# reciever.net
KiCad netlist of a schematic drawn in Altium Designer
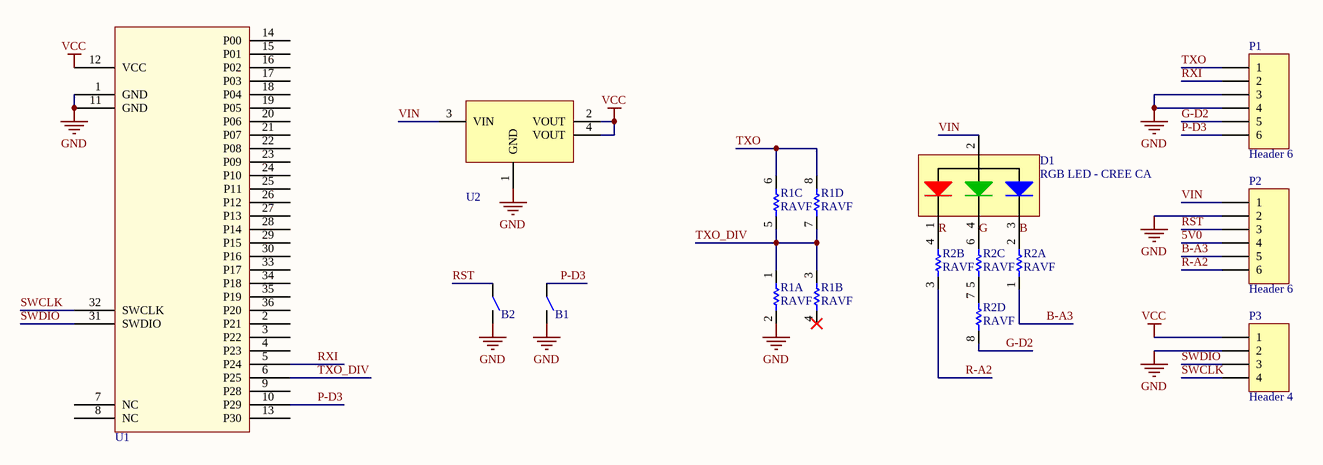
[diagram p0: reciever.SchDoc]

(export (version "E")
  (design (tool "Eeschema 10.0.6"))
  (components
    (comp (ref "B1")
      (value "Tactile Button")
      (footprint "TACTILE BUTTON")
      (libsource (lib "SK") (part "Tactile Button"))
    )
    (comp (ref "B2")
      (value "Tactile Button")
      (footprint "TACTILE BUTTON")
      (libsource (lib "SK") (part "Tactile Button"))
    )
    (comp (ref "D1")
      (value "RGB LED - CREE CA")
      (footprint "PLCC4-RGBLED")
      (description "Tri Colour CA RGB LEDs - CLV1A-FKB")
      (libsource (lib "SK") (part "RGB LED - CREE CA"))
    )
    (comp (ref "P1")
      (value "Header 6")
      (footprint "HDR1X6")
      (description "Header, 6-Pin")
      (fields (field (name "PUBLISHER") "Altium Limited"))
      (libsource (lib "Miscellaneous Connectors") (part "Header 6"))
    )
    (comp (ref "P2")
      (value "Header 6")
      (footprint "HDR1X6")
      (description "Header, 6-Pin")
      (fields (field (name "PUBLISHER") "Altium Limited"))
      (libsource (lib "Miscellaneous Connectors") (part "Header 6"))
    )
    (comp (ref "P3")
      (value "Header 4")
      (footprint "HDR1X4")
      (description "Header, 4-Pin")
      (fields (field (name "PUBLISHER") "Altium Limited"))
      (libsource (lib "Miscellaneous Connectors") (part "Header 4"))
    )
    (comp (ref "R1")
      (value "RAVF")
      (footprint "1206 quad res")
      (description "RAVF164DJT100R")
      (libsource (lib "SK") (part "RAVF_Multi"))
    )
    (comp (ref "R2")
      (value "RAVF")
      (footprint "1206 quad res")
      (description "RAVF164DJT100R")
      (libsource (lib "SK") (part "RAVF_Multi"))
    )
    (comp (ref "U1")
      (value "Core51822 (B)")
      (footprint "Core51822 (B)")
      (description "NRF51822 (B)")
      (libsource (lib "SK") (part "Core51822 (B)"))
    )
    (comp (ref "U2")
      (value "NCP1117")
      (footprint "SOT230P700X180-4N")
      (libsource (lib "SK") (part "NCP1117"))
    )
  )
  (nets
    (net (code "1") (name "/5V0") (class "Default")
      (node (ref "P2") (pin "4") (pinfunction "4_4") (pintype "passive"))
    )
    (net (code "2") (name "/B") (class "Default")
      (node (ref "D1") (pin "3") (pinfunction "B_3") (pintype "passive"))
      (node (ref "R2") (pin "2") (pinfunction "2_2") (pintype "passive"))
    )
    (net (code "3") (name "/B-A3") (class "Default")
      (node (ref "P2") (pin "5") (pinfunction "5_5") (pintype "passive"))
      (node (ref "R2") (pin "1") (pinfunction "1_1") (pintype "passive"))
    )
    (net (code "4") (name "/G") (class "Default")
      (node (ref "D1") (pin "4") (pinfunction "G_4") (pintype "passive"))
      (node (ref "R2") (pin "6") (pinfunction "2_6") (pintype "passive"))
    )
    (net (code "5") (name "/G-D2") (class "Default")
      (node (ref "P1") (pin "5") (pinfunction "5_5") (pintype "passive"))
      (node (ref "R2") (pin "8") (pinfunction "2_8") (pintype "passive"))
    )
    (net (code "6") (name "/P-D3") (class "Default")
      (node (ref "B1") (pin "1") (pinfunction "1_1") (pintype "passive"))
      (node (ref "P1") (pin "6") (pinfunction "6_6") (pintype "passive"))
      (node (ref "U1") (pin "10") (pinfunction "P29_10") (pintype "passive"))
    )
    (net (code "7") (name "/R") (class "Default")
      (node (ref "D1") (pin "1") (pinfunction "R_1") (pintype "passive"))
      (node (ref "R2") (pin "4") (pinfunction "2_4") (pintype "passive"))
    )
    (net (code "8") (name "/R-A2") (class "Default")
      (node (ref "P2") (pin "6") (pinfunction "6_6") (pintype "passive"))
      (node (ref "R2") (pin "3") (pinfunction "1_3") (pintype "passive"))
    )
    (net (code "9") (name "/RST") (class "Default")
      (node (ref "B2") (pin "1") (pinfunction "1_1") (pintype "passive"))
      (node (ref "P2") (pin "3") (pinfunction "3_3") (pintype "passive"))
    )
    (net (code "10") (name "/RXI") (class "Default")
      (node (ref "P1") (pin "2") (pinfunction "2_2") (pintype "passive"))
      (node (ref "U1") (pin "5") (pinfunction "P24_5") (pintype "passive"))
    )
    (net (code "11") (name "/SWCLK") (class "Default")
      (node (ref "P3") (pin "4") (pinfunction "4_4") (pintype "passive"))
      (node (ref "U1") (pin "32") (pinfunction "SWCLK_32") (pintype "passive"))
    )
    (net (code "12") (name "/SWDIO") (class "Default")
      (node (ref "P3") (pin "3") (pinfunction "3_3") (pintype "passive"))
      (node (ref "U1") (pin "31") (pinfunction "SWDIO_31") (pintype "passive"))
    )
    (net (code "13") (name "/TXO") (class "Default")
      (node (ref "P1") (pin "1") (pinfunction "1_1") (pintype "passive"))
      (node (ref "R1") (pin "6") (pinfunction "2_6") (pintype "passive"))
      (node (ref "R1") (pin "8") (pinfunction "2_8") (pintype "passive"))
    )
    (net (code "14") (name "/TXO_DIV") (class "Default")
      (node (ref "R1") (pin "1") (pinfunction "1_1") (pintype "passive"))
      (node (ref "R1") (pin "3") (pinfunction "1_3") (pintype "passive"))
      (node (ref "R1") (pin "5") (pinfunction "1_5") (pintype "passive"))
      (node (ref "R1") (pin "7") (pinfunction "1_7") (pintype "passive"))
      (node (ref "U1") (pin "6") (pinfunction "P25_6") (pintype "passive"))
    )
    (net (code "15") (name "/VIN") (class "Default")
      (node (ref "D1") (pin "2") (pinfunction "CA_2") (pintype "passive"))
      (node (ref "P2") (pin "1") (pinfunction "1_1") (pintype "passive"))
      (node (ref "U2") (pin "3") (pinfunction "VIN_3") (pintype "passive"))
    )
    (net (code "16") (name "GND") (class "Default")
      (node (ref "B1") (pin "2") (pinfunction "2_2") (pintype "passive"))
      (node (ref "B2") (pin "2") (pinfunction "2_2") (pintype "passive"))
      (node (ref "P1") (pin "3") (pinfunction "3_3") (pintype "passive"))
      (node (ref "P1") (pin "4") (pinfunction "4_4") (pintype "passive"))
      (node (ref "P2") (pin "2") (pinfunction "2_2") (pintype "passive"))
      (node (ref "P3") (pin "2") (pinfunction "2_2") (pintype "passive"))
      (node (ref "R1") (pin "2") (pinfunction "2_2") (pintype "passive"))
      (node (ref "U1") (pin "1") (pinfunction "GND_1") (pintype "passive"))
      (node (ref "U1") (pin "11") (pinfunction "GND_11") (pintype "passive"))
      (node (ref "U2") (pin "1") (pinfunction "GND_1") (pintype "passive"))
    )
    (net (code "17") (name "Net-(R2C-1)") (class "Default")
      (node (ref "R2") (pin "5") (pinfunction "1_5") (pintype "passive"))
      (node (ref "R2") (pin "7") (pinfunction "1_7") (pintype "passive"))
    )
    (net (code "18") (name "VCC") (class "Default")
      (node (ref "P3") (pin "1") (pinfunction "1_1") (pintype "passive"))
      (node (ref "U1") (pin "12") (pinfunction "VCC_12") (pintype "passive"))
      (node (ref "U2") (pin "2") (pinfunction "VOUT_2") (pintype "passive"))
      (node (ref "U2") (pin "4") (pinfunction "VOUT_4") (pintype "passive"))
    )
    (net (code "19") (name "unconnected-(R1B-2-Pad4)") (class "Default")
      (node (ref "R1") (pin "4") (pinfunction "2_4") (pintype "passive+no_connect"))
    )
    (net (code "20") (name "unconnected-(U1-NC-Pad7)") (class "Default")
      (node (ref "U1") (pin "7") (pinfunction "NC_7") (pintype "passive"))
    )
    (net (code "21") (name "unconnected-(U1-NC-Pad8)") (class "Default")
      (node (ref "U1") (pin "8") (pinfunction "NC_8") (pintype "passive"))
    )
    (net (code "22") (name "unconnected-(U1-P00-Pad14)") (class "Default")
      (node (ref "U1") (pin "14") (pinfunction "P00_14") (pintype "passive"))
    )
    (net (code "23") (name "unconnected-(U1-P01-Pad15)") (class "Default")
      (node (ref "U1") (pin "15") (pinfunction "P01_15") (pintype "passive"))
    )
    (net (code "24") (name "unconnected-(U1-P02-Pad16)") (class "Default")
      (node (ref "U1") (pin "16") (pinfunction "P02_16") (pintype "passive"))
    )
    (net (code "25") (name "unconnected-(U1-P03-Pad17)") (class "Default")
      (node (ref "U1") (pin "17") (pinfunction "P03_17") (pintype "passive"))
    )
    (net (code "26") (name "unconnected-(U1-P04-Pad18)") (class "Default")
      (node (ref "U1") (pin "18") (pinfunction "P04_18") (pintype "passive"))
    )
    (net (code "27") (name "unconnected-(U1-P05-Pad19)") (class "Default")
      (node (ref "U1") (pin "19") (pinfunction "P05_19") (pintype "passive"))
    )
    (net (code "28") (name "unconnected-(U1-P06-Pad20)") (class "Default")
      (node (ref "U1") (pin "20") (pinfunction "P06_20") (pintype "passive"))
    )
    (net (code "29") (name "unconnected-(U1-P07-Pad21)") (class "Default")
      (node (ref "U1") (pin "21") (pinfunction "P07_21") (pintype "passive"))
    )
    (net (code "30") (name "unconnected-(U1-P08-Pad22)") (class "Default")
      (node (ref "U1") (pin "22") (pinfunction "P08_22") (pintype "passive"))
    )
    (net (code "31") (name "unconnected-(U1-P09-Pad23)") (class "Default")
      (node (ref "U1") (pin "23") (pinfunction "P09_23") (pintype "passive"))
    )
    (net (code "32") (name "unconnected-(U1-P10-Pad24)") (class "Default")
      (node (ref "U1") (pin "24") (pinfunction "P10_24") (pintype "passive"))
    )
    (net (code "33") (name "unconnected-(U1-P11-Pad25)") (class "Default")
      (node (ref "U1") (pin "25") (pinfunction "P11_25") (pintype "passive"))
    )
    (net (code "34") (name "unconnected-(U1-P12-Pad26)") (class "Default")
      (node (ref "U1") (pin "26") (pinfunction "P12_26") (pintype "passive"))
    )
    (net (code "35") (name "unconnected-(U1-P13-Pad27)") (class "Default")
      (node (ref "U1") (pin "27") (pinfunction "P13_27") (pintype "passive"))
    )
    (net (code "36") (name "unconnected-(U1-P14-Pad28)") (class "Default")
      (node (ref "U1") (pin "28") (pinfunction "P14_28") (pintype "passive"))
    )
    (net (code "37") (name "unconnected-(U1-P15-Pad29)") (class "Default")
      (node (ref "U1") (pin "29") (pinfunction "P15_29") (pintype "passive"))
    )
    (net (code "38") (name "unconnected-(U1-P16-Pad30)") (class "Default")
      (node (ref "U1") (pin "30") (pinfunction "P16_30") (pintype "passive"))
    )
    (net (code "39") (name "unconnected-(U1-P17-Pad33)") (class "Default")
      (node (ref "U1") (pin "33") (pinfunction "P17_33") (pintype "passive"))
    )
    (net (code "40") (name "unconnected-(U1-P18-Pad34)") (class "Default")
      (node (ref "U1") (pin "34") (pinfunction "P18_34") (pintype "passive"))
    )
    (net (code "41") (name "unconnected-(U1-P19-Pad35)") (class "Default")
      (node (ref "U1") (pin "35") (pinfunction "P19_35") (pintype "passive"))
    )
    (net (code "42") (name "unconnected-(U1-P20-Pad36)") (class "Default")
      (node (ref "U1") (pin "36") (pinfunction "P20_36") (pintype "passive"))
    )
    (net (code "43") (name "unconnected-(U1-P21-Pad2)") (class "Default")
      (node (ref "U1") (pin "2") (pinfunction "P21_2") (pintype "passive"))
    )
    (net (code "44") (name "unconnected-(U1-P22-Pad3)") (class "Default")
      (node (ref "U1") (pin "3") (pinfunction "P22_3") (pintype "passive"))
    )
    (net (code "45") (name "unconnected-(U1-P23-Pad4)") (class "Default")
      (node (ref "U1") (pin "4") (pinfunction "P23_4") (pintype "passive"))
    )
    (net (code "46") (name "unconnected-(U1-P28-Pad9)") (class "Default")
      (node (ref "U1") (pin "9") (pinfunction "P28_9") (pintype "passive"))
    )
    (net (code "47") (name "unconnected-(U1-P30-Pad13)") (class "Default")
      (node (ref "U1") (pin "13") (pinfunction "P30_13") (pintype "passive"))
    )
  )
)
